# schematic.net
KiCad netlist of a schematic drawn in EAGLE
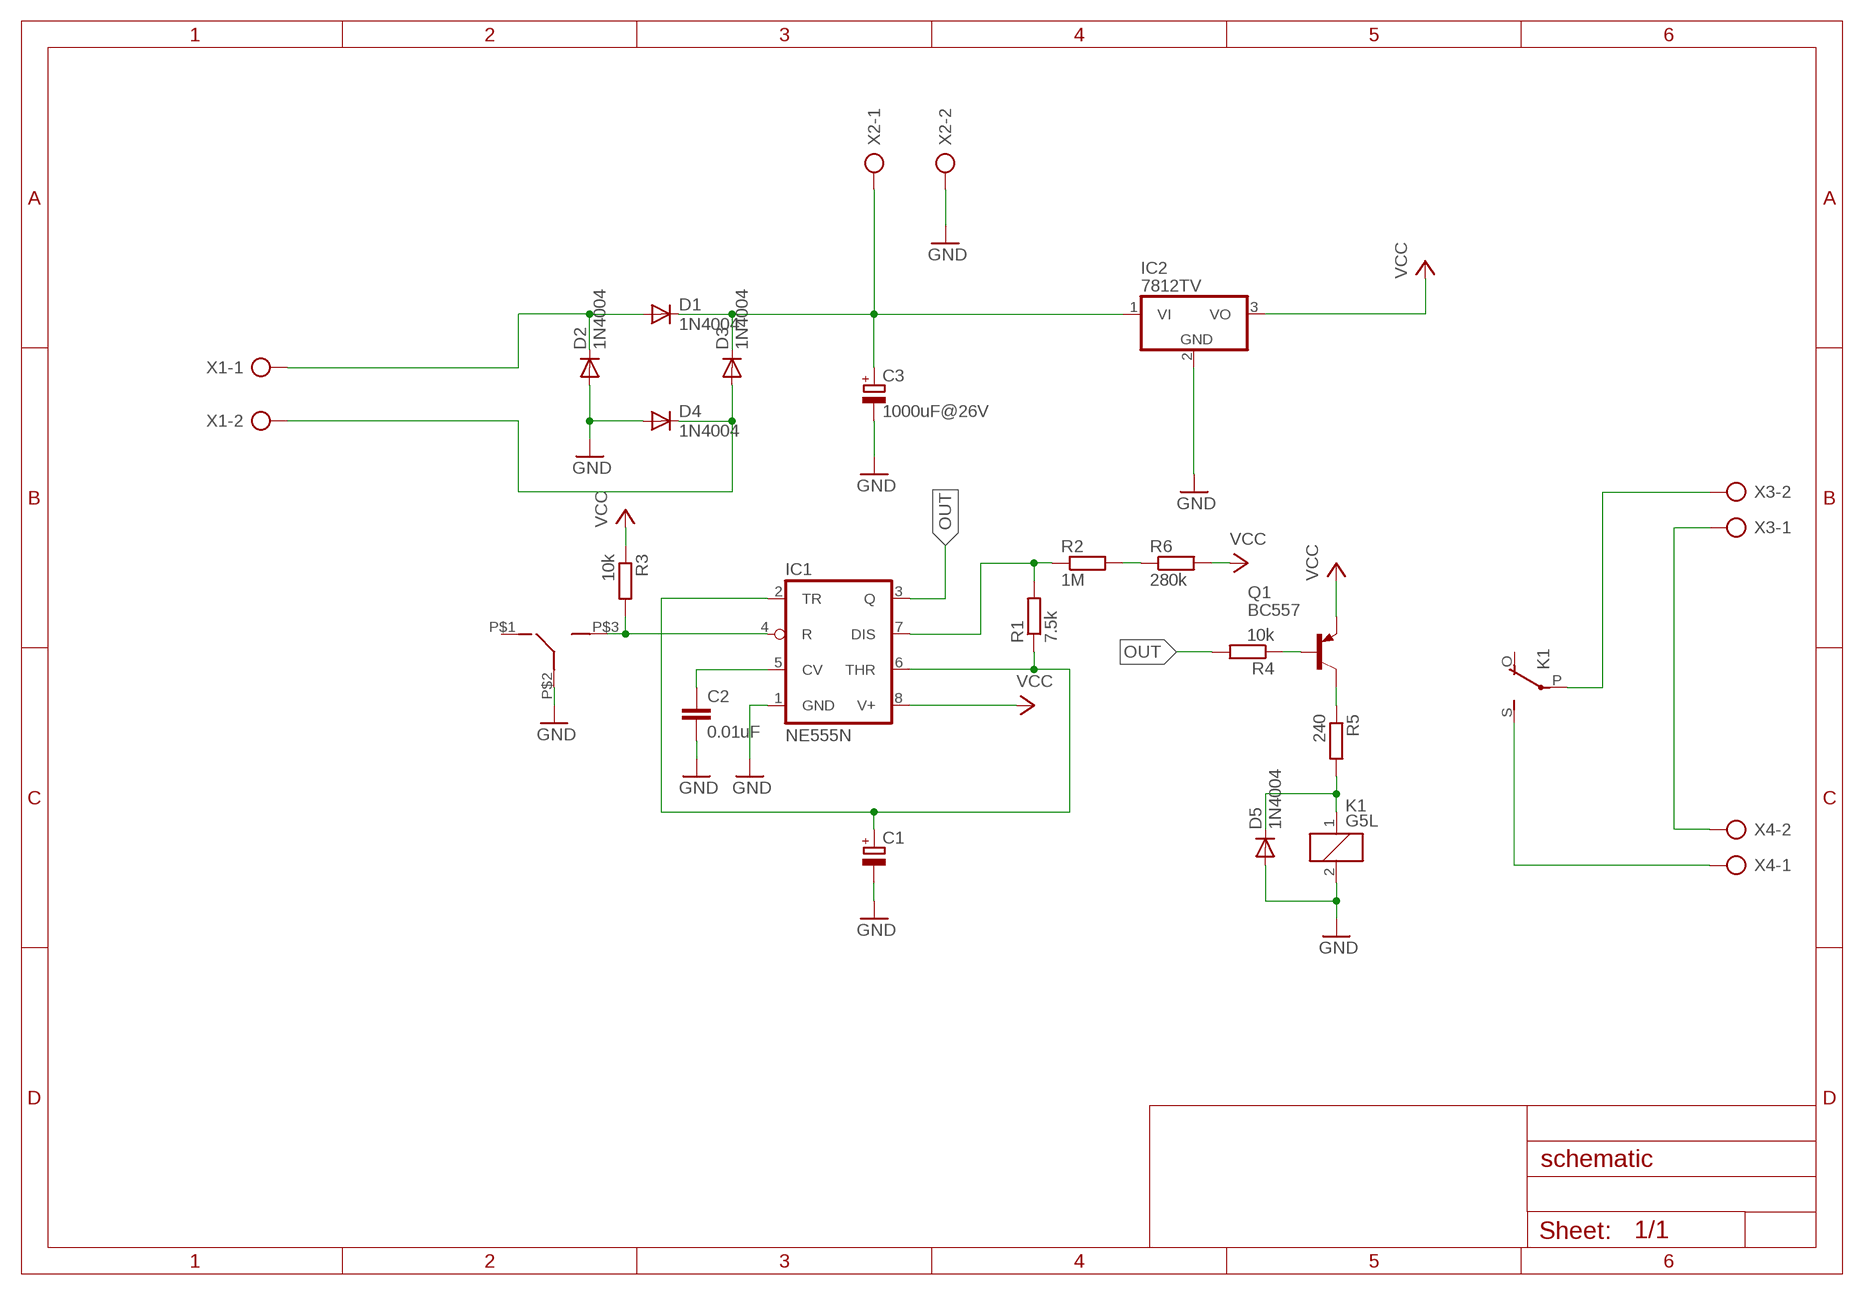
[diagram p0: schematic, sheet 1]

(export (version "E")
  (design (tool "Eeschema 10.0.6"))
  (components
    (comp (ref "C1")
      (value "CPOL-EUE5-13")
      (footprint "eagle-import:E5-13")
      (libsource (lib "eagle-import") (part "CPOL-EUE5-13"))
    )
    (comp (ref "C2")
      (value "0.01uF")
      (footprint "eagle-import:C025-025X050")
      (libsource (lib "eagle-import") (part "C-EU025-025X050"))
    )
    (comp (ref "C3")
      (value "1000uF@26V")
      (footprint "eagle-import:E5-13")
      (libsource (lib "eagle-import") (part "CPOL-EUE5-13"))
    )
    (comp (ref "D1")
      (value "1N4004")
      (footprint "eagle-import:DO41-10")
      (libsource (lib "eagle-import") (part "1N4004"))
    )
    (comp (ref "D2")
      (value "1N4004")
      (footprint "eagle-import:DO41-10")
      (libsource (lib "eagle-import") (part "1N4004"))
    )
    (comp (ref "D3")
      (value "1N4004")
      (footprint "eagle-import:DO41-10")
      (libsource (lib "eagle-import") (part "1N4004"))
    )
    (comp (ref "D4")
      (value "1N4004")
      (footprint "eagle-import:DO41-10")
      (libsource (lib "eagle-import") (part "1N4004"))
    )
    (comp (ref "D5")
      (value "1N4004")
      (footprint "eagle-import:DO41-10")
      (libsource (lib "eagle-import") (part "1N4004"))
    )
    (comp (ref "IC1")
      (value "NE555N")
      (footprint "eagle-import:DIL08")
      (libsource (lib "eagle-import") (part "555NNE"))
    )
    (comp (ref "IC2")
      (value "7812TV")
      (footprint "eagle-import:TO220V")
      (libsource (lib "eagle-import") (part "78TV12"))
    )
    (comp (ref "K1")
      (value "G5L")
      (footprint "eagle-import:G5LE")
      (libsource (lib "eagle-import") (part "G5L"))
    )
    (comp (ref "Q1")
      (value "BC557")
      (footprint "eagle-import:TO92")
      (libsource (lib "eagle-import") (part "BC557"))
    )
    (comp (ref "R1")
      (value "7.5k")
      (footprint "eagle-import:0207_7")
      (libsource (lib "eagle-import") (part "R-EU_0207/7"))
    )
    (comp (ref "R2")
      (value "1M")
      (footprint "eagle-import:0207_7")
      (libsource (lib "eagle-import") (part "R-EU_0207/7"))
    )
    (comp (ref "R3")
      (value "10k")
      (footprint "eagle-import:0207_7")
      (libsource (lib "eagle-import") (part "R-EU_0207/7"))
    )
    (comp (ref "R4")
      (value "10k")
      (footprint "eagle-import:0207_7")
      (libsource (lib "eagle-import") (part "R-EU_0207/7"))
    )
    (comp (ref "R5")
      (value "240")
      (footprint "eagle-import:0207_7")
      (libsource (lib "eagle-import") (part "R-EU_0207/7"))
    )
    (comp (ref "R6")
      (value "280k")
      (footprint "eagle-import:0207_7")
      (libsource (lib "eagle-import") (part "R-EU_0207/7"))
    )
    (comp (ref "SW1")
      (value "SWITCH")
      (footprint "eagle-import:SWITCH")
      (libsource (lib "eagle-import") (part "SWITCH"))
    )
    (comp (ref "X1")
      (value "AK500/2")
      (footprint "eagle-import:AK500_2")
      (libsource (lib "eagle-import") (part "AK500/2"))
    )
    (comp (ref "X2")
      (value "AK500/2")
      (footprint "eagle-import:AK500_2")
      (libsource (lib "eagle-import") (part "AK500/2"))
    )
    (comp (ref "X3")
      (value "AK500/2")
      (footprint "eagle-import:AK500_2")
      (libsource (lib "eagle-import") (part "AK500/2"))
    )
    (comp (ref "X4")
      (value "AK500/2")
      (footprint "eagle-import:AK500_2")
      (libsource (lib "eagle-import") (part "AK500/2"))
    )
  )
  (nets
    (net (code "1") (name "GND") (class "Default")
      (node (ref "C1") (pin "-") (pinfunction "-_-") (pintype "passive"))
      (node (ref "C2") (pin "2") (pinfunction "2_2") (pintype "passive"))
      (node (ref "C3") (pin "-") (pinfunction "-_-") (pintype "passive"))
      (node (ref "D2") (pin "A") (pinfunction "A_A") (pintype "passive"))
      (node (ref "D4") (pin "A") (pinfunction "A_A") (pintype "passive"))
      (node (ref "D5") (pin "A") (pinfunction "A_A") (pintype "passive"))
      (node (ref "IC1") (pin "1") (pinfunction "GND_1") (pintype "power_in"))
      (node (ref "IC2") (pin "2") (pinfunction "GND_2") (pintype "passive"))
      (node (ref "K1") (pin "2") (pinfunction "2_2") (pintype "passive"))
      (node (ref "SW1") (pin "P$2") (pinfunction "P$2_P$2") (pintype "bidirectional"))
      (node (ref "X2") (pin "2") (pinfunction "KL_2") (pintype "passive"))
    )
    (net (code "2") (name "Net-(D5-PadC)") (class "Default")
      (node (ref "D5") (pin "C") (pinfunction "C_C") (pintype "passive"))
      (node (ref "K1") (pin "1") (pinfunction "1_1") (pintype "passive"))
      (node (ref "R5") (pin "2") (pinfunction "2_2") (pintype "passive"))
    )
    (net (code "3") (name "Net-(IC1-CV)") (class "Default")
      (node (ref "C2") (pin "1") (pinfunction "1_1") (pintype "passive"))
      (node (ref "IC1") (pin "5") (pinfunction "CV_5") (pintype "input"))
    )
    (net (code "4") (name "Net-(IC1-DIS)") (class "Default")
      (node (ref "IC1") (pin "7") (pinfunction "DIS_7") (pintype "input"))
      (node (ref "R1") (pin "2") (pinfunction "2_2") (pintype "passive"))
      (node (ref "R2") (pin "1") (pinfunction "1_1") (pintype "passive"))
    )
    (net (code "5") (name "Net-(IC1-R)") (class "Default")
      (node (ref "IC1") (pin "4") (pinfunction "R_4") (pintype "input"))
      (node (ref "R3") (pin "2") (pinfunction "2_2") (pintype "passive"))
      (node (ref "SW1") (pin "P$3") (pinfunction "P$3_P$3") (pintype "bidirectional"))
    )
    (net (code "6") (name "Net-(IC1-THR)") (class "Default")
      (node (ref "C1") (pin "+") (pinfunction "+_+") (pintype "passive"))
      (node (ref "IC1") (pin "2") (pinfunction "TR_2") (pintype "input"))
      (node (ref "IC1") (pin "6") (pinfunction "THR_6") (pintype "input"))
      (node (ref "R1") (pin "1") (pinfunction "1_1") (pintype "passive"))
    )
    (net (code "7") (name "Net-(IC2-VI)") (class "Default")
      (node (ref "C3") (pin "+") (pinfunction "+_+") (pintype "passive"))
      (node (ref "D1") (pin "C") (pinfunction "C_C") (pintype "passive"))
      (node (ref "D3") (pin "C") (pinfunction "C_C") (pintype "passive"))
      (node (ref "IC2") (pin "1") (pinfunction "VI_1") (pintype "input"))
      (node (ref "X2") (pin "1") (pinfunction "KL_1") (pintype "passive"))
    )
    (net (code "8") (name "Net-(Q1-B)") (class "Default")
      (node (ref "Q1") (pin "2") (pinfunction "B_2") (pintype "passive"))
      (node (ref "R4") (pin "1") (pinfunction "1_1") (pintype "passive"))
    )
    (net (code "9") (name "Net-(Q1-C)") (class "Default")
      (node (ref "Q1") (pin "3") (pinfunction "C_3") (pintype "passive"))
      (node (ref "R5") (pin "1") (pinfunction "1_1") (pintype "passive"))
    )
    (net (code "10") (name "Net-(R2-Pad2)") (class "Default")
      (node (ref "R2") (pin "2") (pinfunction "2_2") (pintype "passive"))
      (node (ref "R6") (pin "1") (pinfunction "1_1") (pintype "passive"))
    )
    (net (code "11") (name "Net-(X1A-KL)") (class "Default")
      (node (ref "D1") (pin "A") (pinfunction "A_A") (pintype "passive"))
      (node (ref "D2") (pin "C") (pinfunction "C_C") (pintype "passive"))
      (node (ref "X1") (pin "1") (pinfunction "KL_1") (pintype "passive"))
    )
    (net (code "12") (name "Net-(X1B-KL)") (class "Default")
      (node (ref "D3") (pin "A") (pinfunction "A_A") (pintype "passive"))
      (node (ref "D4") (pin "C") (pinfunction "C_C") (pintype "passive"))
      (node (ref "X1") (pin "2") (pinfunction "KL_2") (pintype "passive"))
    )
    (net (code "13") (name "Net-(X3A-KL)") (class "Default")
      (node (ref "X3") (pin "1") (pinfunction "KL_1") (pintype "passive"))
      (node (ref "X4") (pin "2") (pinfunction "KL_2") (pintype "passive"))
    )
    (net (code "14") (name "Net-(X3B-KL)") (class "Default")
      (node (ref "K1") (pin "P") (pinfunction "P_P") (pintype "passive"))
      (node (ref "X3") (pin "2") (pinfunction "KL_2") (pintype "passive"))
    )
    (net (code "15") (name "Net-(X4A-KL)") (class "Default")
      (node (ref "K1") (pin "S") (pinfunction "S_S") (pintype "passive"))
      (node (ref "X4") (pin "1") (pinfunction "KL_1") (pintype "passive"))
    )
    (net (code "16") (name "OUT") (class "Default")
      (node (ref "IC1") (pin "3") (pinfunction "Q_3") (pintype "output"))
      (node (ref "R4") (pin "2") (pinfunction "2_2") (pintype "passive"))
    )
    (net (code "17") (name "VCC") (class "Default")
      (node (ref "IC1") (pin "8") (pinfunction "V+_8") (pintype "power_in"))
      (node (ref "IC2") (pin "3") (pinfunction "VO_3") (pintype "passive"))
      (node (ref "Q1") (pin "1") (pinfunction "E_1") (pintype "passive"))
      (node (ref "R3") (pin "1") (pinfunction "1_1") (pintype "passive"))
      (node (ref "R6") (pin "2") (pinfunction "2_2") (pintype "passive"))
    )
    (net (code "18") (name "unconnected-(K1-PadO)") (class "Default")
      (node (ref "K1") (pin "O") (pinfunction "O_O") (pintype "passive"))
    )
    (net (code "19") (name "unconnected-(SW1-PadP$1)") (class "Default")
      (node (ref "SW1") (pin "P$1") (pinfunction "P$1_P$1") (pintype "bidirectional"))
    )
  )
)
